# Schematic_sram_dram_mosfet.net
KiCad netlist of a schematic drawn in EasyEDA
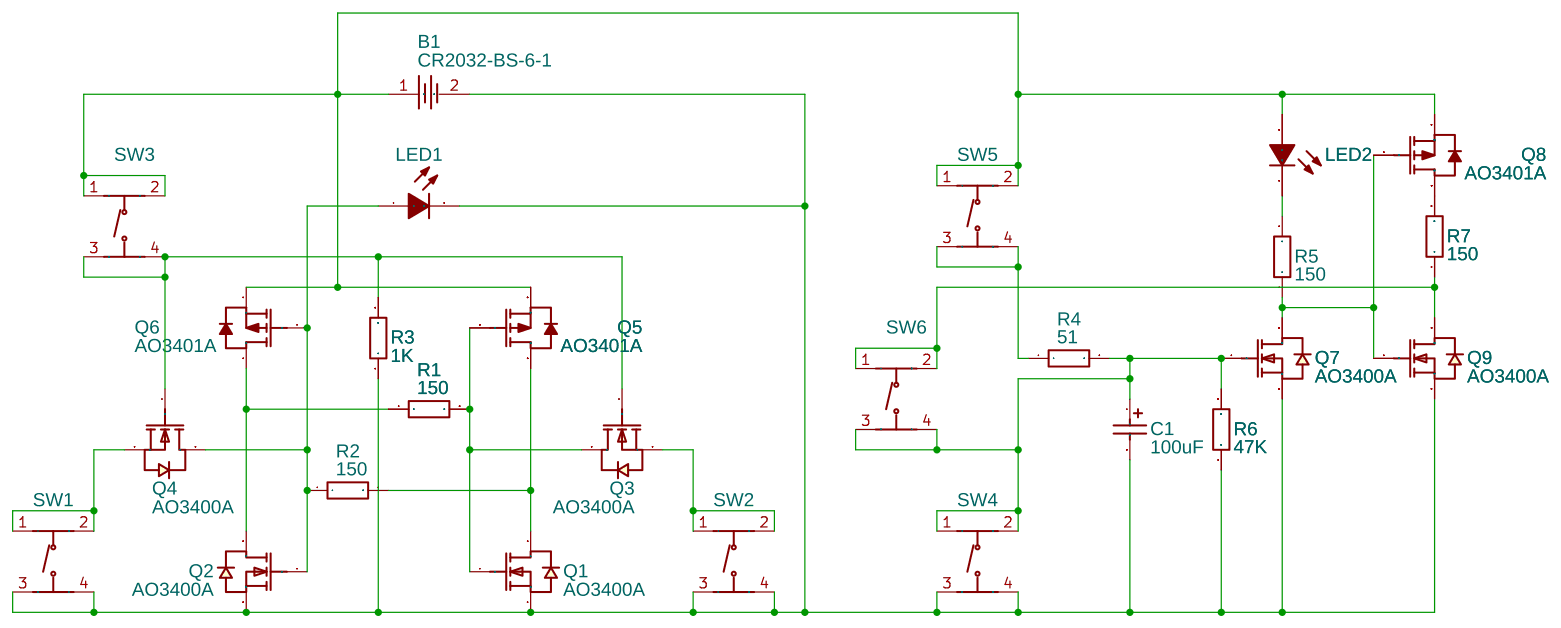
[diagram p0: schematic sheet]

(export (version "E")
  (design (tool "Eeschema 10.0.6"))
  (components
    (comp (ref "B1")
      (value "CR2032-BS-6-1")
      (fields (field (name "BOM_Supplier Part") "C70377"))
      (libsource (lib "") (part "CR2032-BS-6-1"))
    )
    (comp (ref "C1")
      (value "100uF")
      (fields
        (field (name "BOM_Manufacturer Part") "TAJB107K006RNJ")
        (field (name "BOM_Supplier Part") "C16133")
      )
      (libsource (lib "") (part "TAJB107K006RNJ"))
    )
    (comp (ref "LED1")
      (value "19-213/Y2C-CQ2R2L/3T(CY)")
      (fields (field (name "BOM_Supplier Part") "C72038"))
      (libsource (lib "") (part "19-213/Y2C-CQ2R2L/3T(CY)_1"))
    )
    (comp (ref "LED2")
      (value "19-213/Y2C-CQ2R2L/3T(CY)")
      (fields (field (name "BOM_Supplier Part") "C72038"))
      (libsource (lib "") (part "19-213/Y2C-CQ2R2L/3T(CY)"))
    )
    (comp (ref "Q1")
      (value "AO3400A")
      (fields (field (name "BOM_Supplier Part") "C20917"))
      (libsource (lib "") (part "AO3400A"))
    )
    (comp (ref "Q2")
      (value "AO3400A")
      (fields (field (name "BOM_Supplier Part") "C20917"))
      (libsource (lib "") (part "AO3400A_1"))
    )
    (comp (ref "Q3")
      (value "AO3400A")
      (fields (field (name "BOM_Supplier Part") "C20917"))
      (libsource (lib "") (part "AO3400A_2"))
    )
    (comp (ref "Q4")
      (value "AO3400A")
      (fields (field (name "BOM_Supplier Part") "C20917"))
      (libsource (lib "") (part "AO3400A_3"))
    )
    (comp (ref "Q5")
      (value "AO3401A")
      (fields (field (name "BOM_Supplier Part") "C15127"))
      (libsource (lib "") (part "AO3401A"))
    )
    (comp (ref "Q6")
      (value "AO3401A")
      (fields (field (name "BOM_Supplier Part") "C15127"))
      (libsource (lib "") (part "AO3401A_1"))
    )
    (comp (ref "Q7")
      (value "AO3400A")
      (fields (field (name "BOM_Supplier Part") "C20917"))
      (libsource (lib "") (part "AO3400A"))
    )
    (comp (ref "Q8")
      (value "AO3401A")
      (fields (field (name "BOM_Supplier Part") "C15127"))
      (libsource (lib "") (part "AO3401A"))
    )
    (comp (ref "Q9")
      (value "AO3400A")
      (fields (field (name "BOM_Supplier Part") "C20917"))
      (libsource (lib "") (part "AO3400A"))
    )
    (comp (ref "R1")
      (value "150")
      (fields
        (field (name "BOM_Manufacturer Part") "0603WAF1500T5E")
        (field (name "BOM_Supplier Part") "C22808")
      )
      (libsource (lib "") (part "0603WAF1500T5E"))
    )
    (comp (ref "R2")
      (value "150")
      (fields
        (field (name "BOM_Manufacturer Part") "0603WAF1500T5E")
        (field (name "BOM_Supplier Part") "C22808")
      )
      (libsource (lib "") (part "0603WAF1500T5E"))
    )
    (comp (ref "R3")
      (value "1K")
      (fields
        (field (name "BOM_Manufacturer Part") "0603WAF1001T5E")
        (field (name "BOM_Supplier Part") "C21190")
      )
      (libsource (lib "") (part "0603WAF1001T5E"))
    )
    (comp (ref "R4")
      (value "51")
      (fields
        (field (name "BOM_Manufacturer Part") "0603WAF510JT5E")
        (field (name "BOM_Supplier Part") "C23197")
      )
      (libsource (lib "") (part "0603WAF1500T5E"))
    )
    (comp (ref "R5")
      (value "150")
      (fields
        (field (name "BOM_Manufacturer Part") "0603WAF1500T5E")
        (field (name "BOM_Supplier Part") "C22808")
      )
      (libsource (lib "") (part "0603WAF510JT5E"))
    )
    (comp (ref "R6")
      (value "47K")
      (fields
        (field (name "BOM_Manufacturer Part") "0603WAF4702T5E")
        (field (name "BOM_Supplier Part") "C25819")
      )
      (libsource (lib "") (part "0603WAF2702T5E"))
    )
    (comp (ref "R7")
      (value "150")
      (fields
        (field (name "BOM_Manufacturer Part") "0603WAF1500T5E")
        (field (name "BOM_Supplier Part") "C22808")
      )
      (libsource (lib "") (part "0603WAF1500T5E_1"))
    )
    (comp (ref "SW1")
      (value "TS-1187A-B-A-B")
      (fields (field (name "BOM_Supplier Part") "C318884"))
      (libsource (lib "") (part "TS-1187A-B-A-B"))
    )
    (comp (ref "SW2")
      (value "TS-1187A-B-A-B")
      (fields (field (name "BOM_Supplier Part") "C318884"))
      (libsource (lib "") (part "TS-1187A-B-A-B"))
    )
    (comp (ref "SW3")
      (value "TS-1187A-B-A-B")
      (fields (field (name "BOM_Supplier Part") "C318884"))
      (libsource (lib "") (part "TS-1187A-B-A-B"))
    )
    (comp (ref "SW4")
      (value "TS-1187A-B-A-B")
      (fields (field (name "BOM_Supplier Part") "C318884"))
      (libsource (lib "") (part "TS-1187A-B-A-B"))
    )
    (comp (ref "SW5")
      (value "TS-1187A-B-A-B")
      (fields (field (name "BOM_Supplier Part") "C318884"))
      (libsource (lib "") (part "TS-1187A-B-A-B"))
    )
    (comp (ref "SW6")
      (value "TS-1187A-B-A-B")
      (fields (field (name "BOM_Supplier Part") "C318884"))
      (libsource (lib "") (part "TS-1187A-B-A-B"))
    )
  )
  (nets
    (net (code "1") (name "Net-(LED1-A)") (class "Default")
      (node (ref "LED1") (pin "1") (pinfunction "A_1") (pintype "input"))
      (node (ref "Q2") (pin "1") (pinfunction "G_1") (pintype "unspecified"))
      (node (ref "Q4") (pin "3") (pinfunction "D_3") (pintype "unspecified"))
      (node (ref "Q6") (pin "1") (pinfunction "G_1") (pintype "unspecified"))
      (node (ref "R2") (pin "1") (pinfunction "1_1") (pintype "input"))
    )
    (net (code "2") (name "Net-(LED1-C)") (class "Default")
      (node (ref "B1") (pin "2") (pinfunction "2_2") (pintype "input"))
      (node (ref "C1") (pin "2") (pinfunction "2_2") (pintype "input"))
      (node (ref "LED1") (pin "2") (pinfunction "C_2") (pintype "input"))
      (node (ref "Q1") (pin "2") (pinfunction "S_2") (pintype "unspecified"))
      (node (ref "Q2") (pin "2") (pinfunction "S_2") (pintype "unspecified"))
      (node (ref "Q7") (pin "2") (pinfunction "S_2") (pintype "unspecified"))
      (node (ref "Q9") (pin "2") (pinfunction "S_2") (pintype "unspecified"))
      (node (ref "R3") (pin "1") (pinfunction "1_1") (pintype "input"))
      (node (ref "R6") (pin "1") (pinfunction "1_1") (pintype "input"))
      (node (ref "SW1") (pin "3") (pinfunction "C_3") (pintype "unspecified"))
      (node (ref "SW1") (pin "4") (pinfunction "D_4") (pintype "unspecified"))
      (node (ref "SW2") (pin "3") (pinfunction "C_3") (pintype "unspecified"))
      (node (ref "SW2") (pin "4") (pinfunction "D_4") (pintype "unspecified"))
      (node (ref "SW4") (pin "3") (pinfunction "C_3") (pintype "unspecified"))
      (node (ref "SW4") (pin "4") (pinfunction "D_4") (pintype "unspecified"))
    )
    (net (code "3") (name "Net-(LED2-A)") (class "Default")
      (node (ref "B1") (pin "1") (pinfunction "1_1") (pintype "input"))
      (node (ref "LED2") (pin "1") (pinfunction "A_1") (pintype "input"))
      (node (ref "Q5") (pin "2") (pinfunction "S_2") (pintype "unspecified"))
      (node (ref "Q6") (pin "2") (pinfunction "S_2") (pintype "unspecified"))
      (node (ref "Q8") (pin "2") (pinfunction "S_2") (pintype "unspecified"))
      (node (ref "SW3") (pin "1") (pinfunction "A_1") (pintype "unspecified"))
      (node (ref "SW3") (pin "2") (pinfunction "B_2") (pintype "unspecified"))
      (node (ref "SW5") (pin "1") (pinfunction "A_1") (pintype "unspecified"))
      (node (ref "SW5") (pin "2") (pinfunction "B_2") (pintype "unspecified"))
    )
    (net (code "4") (name "Net-(LED2-C)") (class "Default")
      (node (ref "LED2") (pin "2") (pinfunction "C_2") (pintype "input"))
      (node (ref "R5") (pin "2") (pinfunction "2_2") (pintype "input"))
    )
    (net (code "5") (name "Net-(Q1-D)") (class "Default")
      (node (ref "Q1") (pin "3") (pinfunction "D_3") (pintype "unspecified"))
      (node (ref "Q5") (pin "3") (pinfunction "D_3") (pintype "unspecified"))
      (node (ref "R2") (pin "2") (pinfunction "2_2") (pintype "input"))
    )
    (net (code "6") (name "Net-(Q1-G)") (class "Default")
      (node (ref "Q1") (pin "1") (pinfunction "G_1") (pintype "unspecified"))
      (node (ref "Q3") (pin "3") (pinfunction "D_3") (pintype "unspecified"))
      (node (ref "Q5") (pin "1") (pinfunction "G_1") (pintype "unspecified"))
      (node (ref "R1") (pin "2") (pinfunction "2_2") (pintype "input"))
    )
    (net (code "7") (name "Net-(Q2-D)") (class "Default")
      (node (ref "Q2") (pin "3") (pinfunction "D_3") (pintype "unspecified"))
      (node (ref "Q6") (pin "3") (pinfunction "D_3") (pintype "unspecified"))
      (node (ref "R1") (pin "1") (pinfunction "1_1") (pintype "input"))
    )
    (net (code "8") (name "Net-(Q3-G)") (class "Default")
      (node (ref "Q3") (pin "1") (pinfunction "G_1") (pintype "unspecified"))
      (node (ref "Q4") (pin "1") (pinfunction "G_1") (pintype "unspecified"))
      (node (ref "R3") (pin "2") (pinfunction "2_2") (pintype "input"))
      (node (ref "SW3") (pin "3") (pinfunction "C_3") (pintype "unspecified"))
      (node (ref "SW3") (pin "4") (pinfunction "D_4") (pintype "unspecified"))
    )
    (net (code "9") (name "Net-(Q3-S)") (class "Default")
      (node (ref "Q3") (pin "2") (pinfunction "S_2") (pintype "unspecified"))
      (node (ref "SW2") (pin "1") (pinfunction "A_1") (pintype "unspecified"))
      (node (ref "SW2") (pin "2") (pinfunction "B_2") (pintype "unspecified"))
    )
    (net (code "10") (name "Net-(Q4-S)") (class "Default")
      (node (ref "Q4") (pin "2") (pinfunction "S_2") (pintype "unspecified"))
      (node (ref "SW1") (pin "1") (pinfunction "A_1") (pintype "unspecified"))
      (node (ref "SW1") (pin "2") (pinfunction "B_2") (pintype "unspecified"))
    )
    (net (code "11") (name "Net-(Q7-D)") (class "Default")
      (node (ref "Q7") (pin "3") (pinfunction "D_3") (pintype "unspecified"))
      (node (ref "Q8") (pin "1") (pinfunction "G_1") (pintype "unspecified"))
      (node (ref "Q9") (pin "1") (pinfunction "G_1") (pintype "unspecified"))
      (node (ref "R5") (pin "1") (pinfunction "1_1") (pintype "input"))
    )
    (net (code "12") (name "Net-(Q7-G)") (class "Default")
      (node (ref "C1") (pin "1") (pinfunction "1_1") (pintype "input"))
      (node (ref "Q7") (pin "1") (pinfunction "G_1") (pintype "unspecified"))
      (node (ref "R4") (pin "2") (pinfunction "2_2") (pintype "input"))
      (node (ref "R6") (pin "2") (pinfunction "2_2") (pintype "input"))
      (node (ref "SW4") (pin "1") (pinfunction "A_1") (pintype "unspecified"))
      (node (ref "SW4") (pin "2") (pinfunction "B_2") (pintype "unspecified"))
      (node (ref "SW6") (pin "3") (pinfunction "C_3") (pintype "unspecified"))
      (node (ref "SW6") (pin "4") (pinfunction "D_4") (pintype "unspecified"))
    )
    (net (code "13") (name "Net-(Q8-D)") (class "Default")
      (node (ref "Q8") (pin "3") (pinfunction "D_3") (pintype "unspecified"))
      (node (ref "R7") (pin "2") (pinfunction "2_2") (pintype "input"))
    )
    (net (code "14") (name "Net-(Q9-D)") (class "Default")
      (node (ref "Q9") (pin "3") (pinfunction "D_3") (pintype "unspecified"))
      (node (ref "R7") (pin "1") (pinfunction "1_1") (pintype "input"))
      (node (ref "SW6") (pin "1") (pinfunction "A_1") (pintype "unspecified"))
      (node (ref "SW6") (pin "2") (pinfunction "B_2") (pintype "unspecified"))
    )
    (net (code "15") (name "Net-(SW5-C)") (class "Default")
      (node (ref "R4") (pin "1") (pinfunction "1_1") (pintype "input"))
      (node (ref "SW5") (pin "3") (pinfunction "C_3") (pintype "unspecified"))
      (node (ref "SW5") (pin "4") (pinfunction "D_4") (pintype "unspecified"))
    )
  )
)
